# design.net
KiCad netlist of a schematic drawn in EasyEDA Pro
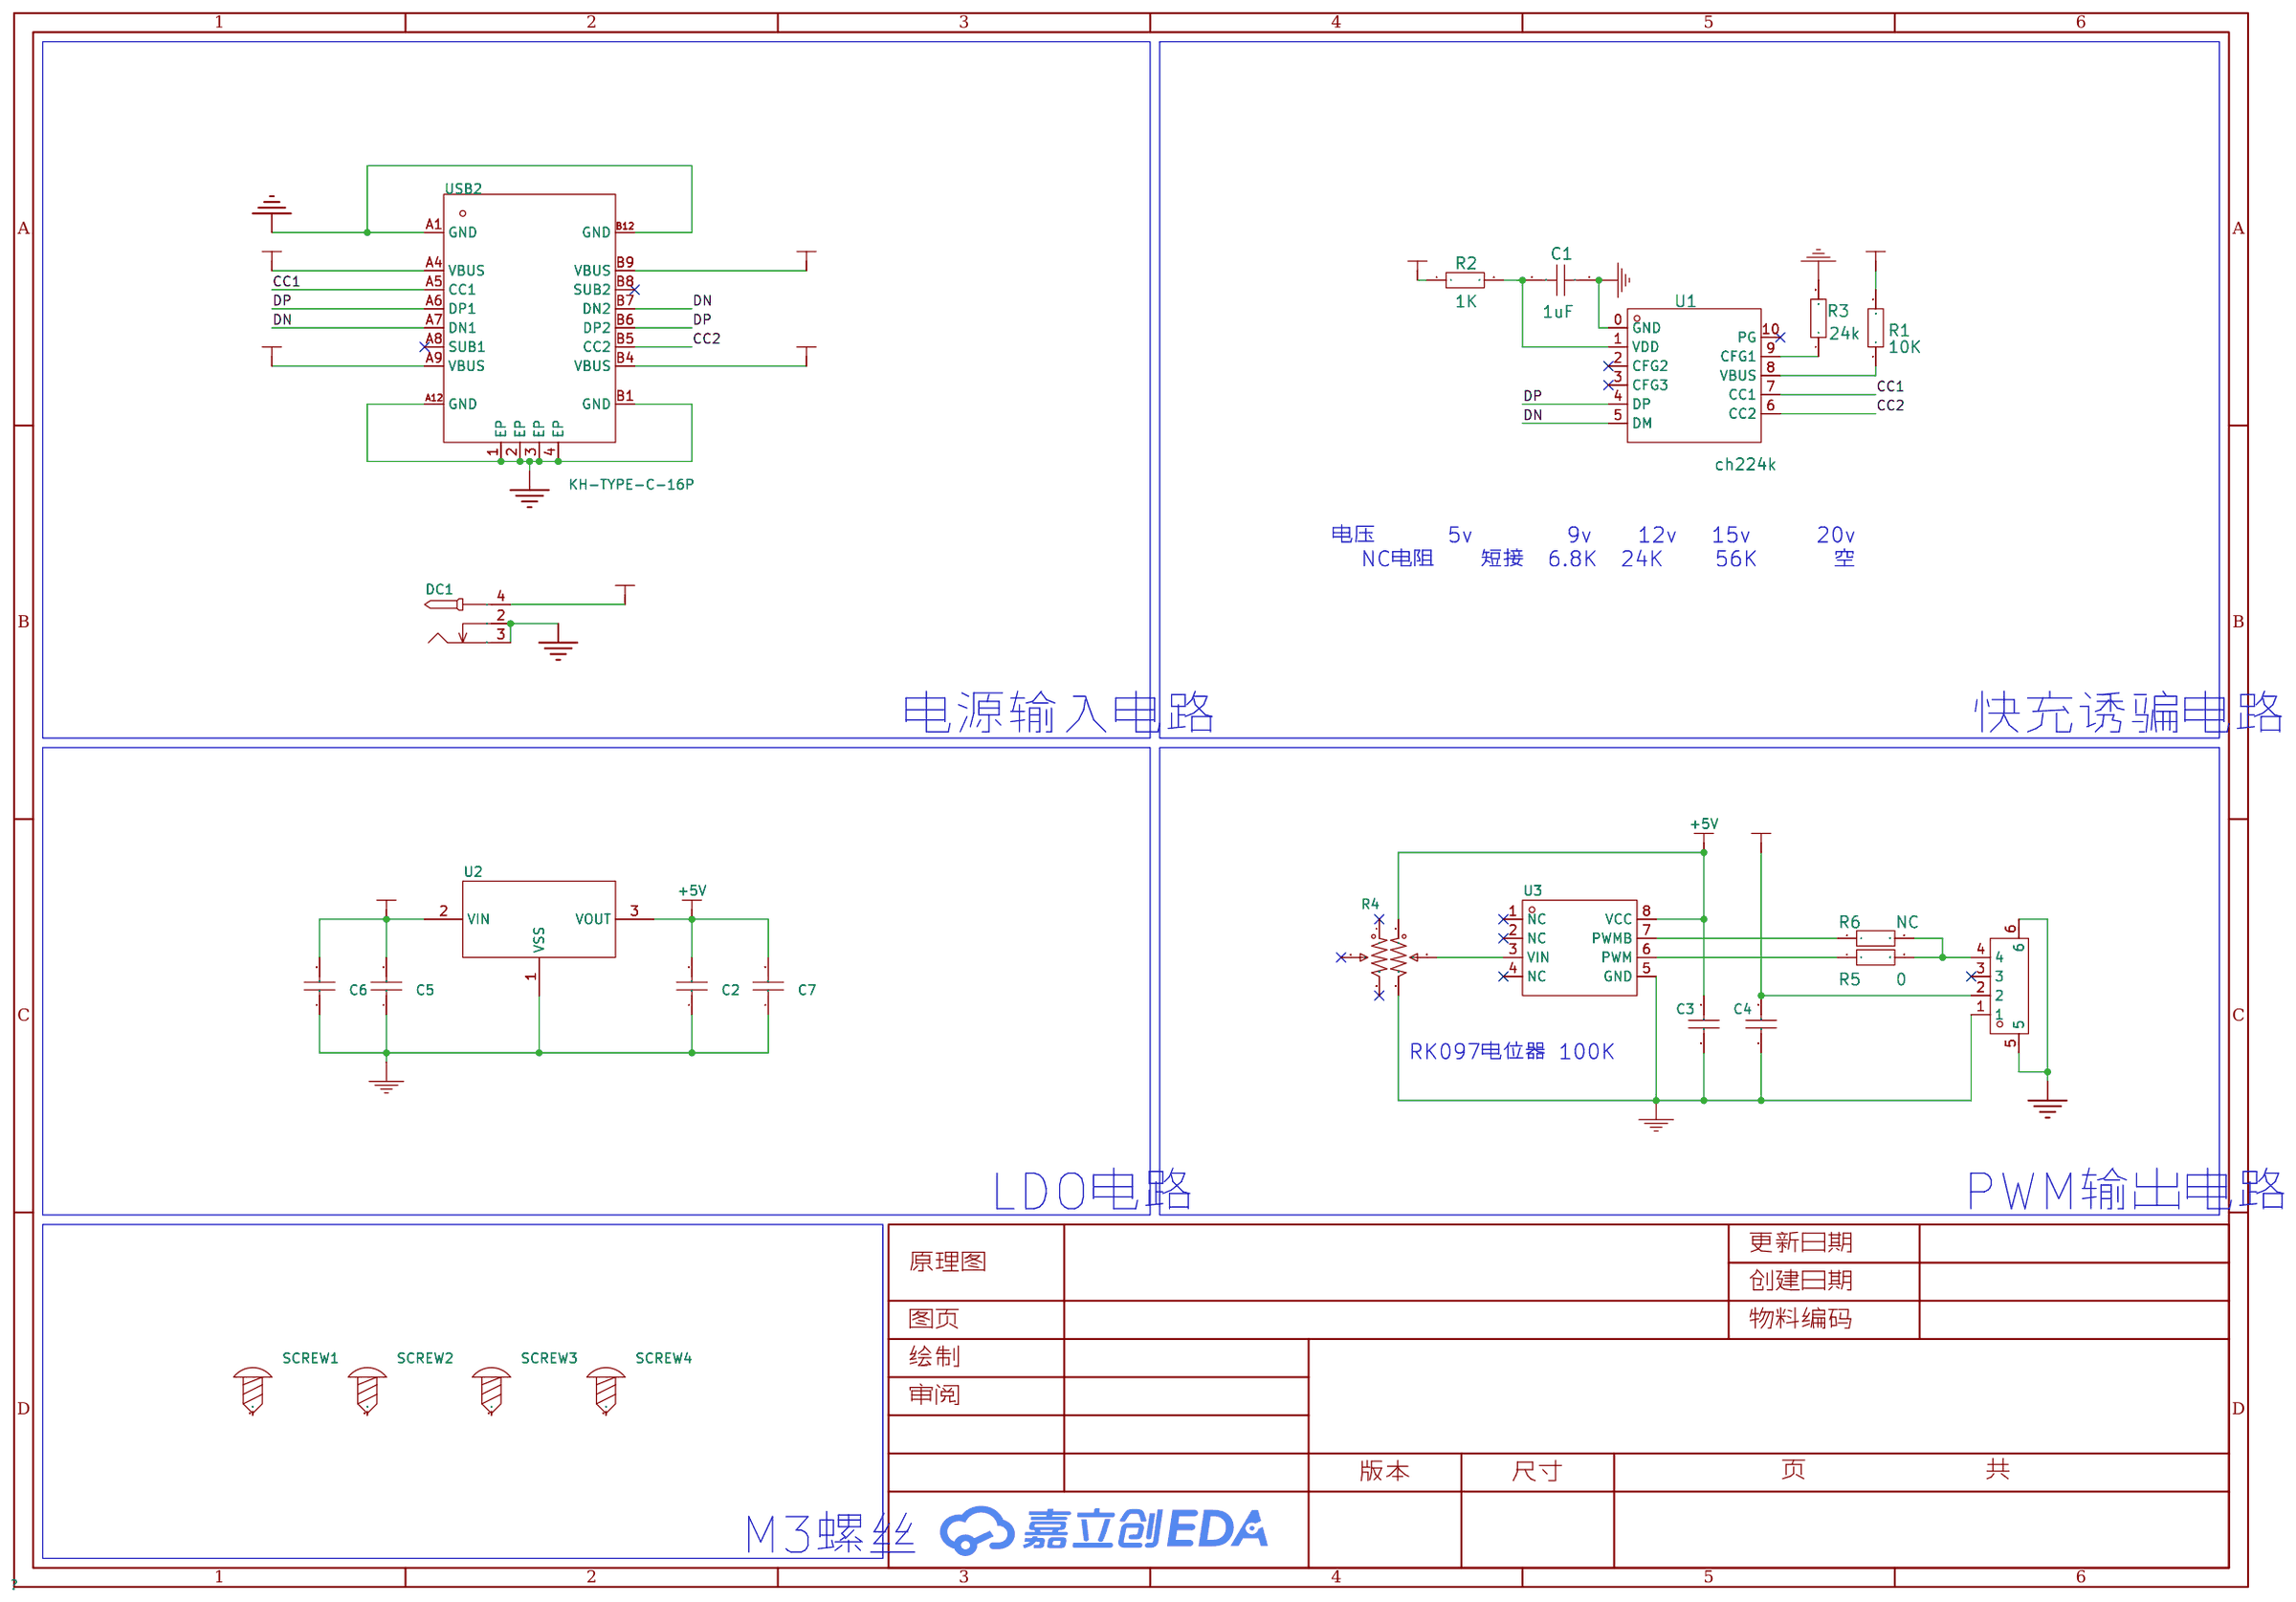
[diagram p0: schematic sheet]

(export (version "E")
  (design (tool "Eeschema 10.0.6"))
  (components
    (comp (ref "C1")
      (value "1uF")
      (footprint "easyedapro:C0805")
      (fields (field (name "Manufacturer Part") "CL10B104KC8NNNC") (field (name "Manufacturer") "SAMSUNG"))
      (libsource (lib "easyedapro") (part "1uF-10uF"))
    )
    (comp (ref "C2")
      (value "10uF")
      (fields
        (field (name "Manufacturer Part") "GRM188R6YA106MA73D")
        (field (name "Manufacturer") "muRata(村田)")
      )
      (libsource (lib "easyedapro") (part "CL10A106MO8NQNC"))
    )
    (comp (ref "C3")
      (value "10uF")
      (fields
        (field (name "Manufacturer Part") "GRM188R6YA106MA73D")
        (field (name "Manufacturer") "muRata(村田)")
      )
      (libsource (lib "easyedapro") (part "CL10A106MO8NQNC"))
    )
    (comp (ref "C4")
      (value "10uF")
      (fields
        (field (name "Manufacturer Part") "GRM188R6YA106MA73D")
        (field (name "Manufacturer") "muRata(村田)")
      )
      (libsource (lib "easyedapro") (part "CL10A106MO8NQNC"))
    )
    (comp (ref "C5")
      (value "10uF")
      (fields
        (field (name "Manufacturer Part") "GRM188R6YA106MA73D")
        (field (name "Manufacturer") "muRata(村田)")
      )
      (libsource (lib "easyedapro") (part "CL10A106MO8NQNC"))
    )
    (comp (ref "C6")
      (value "10uF")
      (fields
        (field (name "Manufacturer Part") "GRM188R6YA106MA73D")
        (field (name "Manufacturer") "muRata(村田)")
      )
      (libsource (lib "easyedapro") (part "CL10A106MO8NQNC"))
    )
    (comp (ref "C7")
      (value "10uF")
      (fields
        (field (name "Manufacturer Part") "GRM188R6YA106MA73D")
        (field (name "Manufacturer") "muRata(村田)")
      )
      (libsource (lib "easyedapro") (part "CL10A106MO8NQNC"))
    )
    (comp (ref "DC1")
      (value "~")
      (footprint "easyedapro:DC-2.0")
      (libsource (lib "easyedapro") (part "DC电源接口"))
    )
    (comp (ref "P2")
      (value "CONN-SMD_XH2.54-4PSMD")
      (footprint "easyedapro:CONN-SMD_XH2.54-4PSMD")
      (libsource (lib "easyedapro") (part "CONN-SMD_XH2.54-4PSMD"))
    )
    (comp (ref "R1")
      (value "10K")
      (footprint "easyedapro:R0805")
      (fields (field (name "Manufacturer Part") "0603WAJ0000T5E") (field (name "Manufacturer") "UniOhm"))
      (libsource (lib "easyedapro") (part "NC"))
    )
    (comp (ref "R2")
      (value "1K")
      (footprint "easyedapro:R0805")
      (fields (field (name "Manufacturer Part") "0603WAJ0000T5E") (field (name "Manufacturer") "UniOhm"))
      (libsource (lib "easyedapro") (part "NC"))
    )
    (comp (ref "R3")
      (value "24k")
      (footprint "easyedapro:R0805")
      (fields (field (name "Manufacturer Part") "0603WAJ0000T5E") (field (name "Manufacturer") "UniOhm"))
      (libsource (lib "easyedapro") (part "NC"))
    )
    (comp (ref "R4")
      (value "100kΩ")
      (footprint "easyedapro:RES-ADJ-TH_RK09712200MY")
      (description "阻值:10kΩ;精度:±20%;")
      (fields
        (field (name "Manufacturer Part") "RK09712200MY")
        (field (name "Manufacturer") "ALPSALPINE(阿尔卑斯阿尔派)")
      )
      (libsource (lib "easyedapro") (part "RK09712200MY"))
    )
    (comp (ref "R5")
      (value "0")
      (footprint "easyedapro:R0805")
      (fields (field (name "Manufacturer Part") "0603WAJ0000T5E") (field (name "Manufacturer") "UniOhm"))
      (libsource (lib "easyedapro") (part "NC"))
    )
    (comp (ref "R6")
      (value "NC")
      (footprint "easyedapro:R0805")
      (fields (field (name "Manufacturer Part") "0603WAJ0000T5E") (field (name "Manufacturer") "UniOhm"))
      (libsource (lib "easyedapro") (part "NC"))
    )
    (comp (ref "SCREW1")
      (value "~")
      (footprint "easyedapro:M3螺丝")
      (libsource (lib "easyedapro") (part "螺丝孔"))
    )
    (comp (ref "SCREW2")
      (value "~")
      (footprint "easyedapro:M3螺丝")
      (libsource (lib "easyedapro") (part "螺丝孔"))
    )
    (comp (ref "SCREW3")
      (value "~")
      (footprint "easyedapro:M3螺丝")
      (libsource (lib "easyedapro") (part "螺丝孔"))
    )
    (comp (ref "SCREW4")
      (value "~")
      (footprint "easyedapro:M3螺丝")
      (libsource (lib "easyedapro") (part "螺丝孔"))
    )
    (comp (ref "U1")
      (value "ch224k")
      (footprint "easyedapro:CH224K")
      (fields (field (name "Manufacturer Part") "CH224DS1") (field (name "Manufacturer") "WCH"))
      (libsource (lib "easyedapro") (part "ch224k"))
    )
    (comp (ref "U2")
      (value "ME6203A50PG")
      (footprint "easyedapro:SOT-89_L4.5-W2.5-P1.50-LS4.2-BR")
      (description "输出类型:固定;输出极性:正;输出通道数:1;最大输入电压:30V;输出电压:5V;压差:-;输出电流:100mA;电源纹波抑制比(PSRR):40dB@(1kHz);")
      (fields (field (name "Manufacturer") "MICRONE(南京微盟)"))
      (libsource (lib "easyedapro") (part "ME6203A50PG"))
    )
    (comp (ref "U3")
      (value "GP9101-F20K-L2H1-SW")
      (footprint "easyedapro:SOP-8_L5.0-W3.9-P1.27-LS6.0-BL")
      (description "GP9101 0-VCC转PWM 20KHz L2H1")
      (fields (field (name "Manufacturer") "Guestgood(客益)"))
      (libsource (lib "easyedapro") (part "GP9101-F20K-L2H1-SW"))
    )
    (comp (ref "USB2")
      (value "KH-TYPE-C-16P")
      (footprint "easyedapro:USB-C-SMD_KH-TYPE-C-16P")
      (description "连接器类型:Type-C;标准:-;公母:母;端口数量:1;触点数量:16P;安装方式:卧贴;额定电流 - 电源:3A;工作温度范围:-40°C~+85°C;")
      (fields (field (name "Manufacturer") "kinghelm(金航标)"))
      (libsource (lib "easyedapro") (part "KH-TYPE-C-16P"))
    )
  )
  (nets
    (net (code "1") (name "+5V") (class "Default")
      (node (ref "C2") (pin "2") (pinfunction "2_2") (pintype "input"))
      (node (ref "C3") (pin "2") (pinfunction "2_2") (pintype "input"))
      (node (ref "C7") (pin "2") (pinfunction "2_2") (pintype "input"))
      (node (ref "R4") (pin "1") (pinfunction "1_1") (pintype "input"))
      (node (ref "U2") (pin "3") (pinfunction "VOUT_3") (pintype "input"))
      (node (ref "U3") (pin "8") (pinfunction "VCC_8") (pintype "input"))
    )
    (net (code "2") (name "+12V") (class "Default")
      (node (ref "C4") (pin "2") (pinfunction "2_2") (pintype "input"))
      (node (ref "C5") (pin "2") (pinfunction "2_2") (pintype "input"))
      (node (ref "C6") (pin "2") (pinfunction "2_2") (pintype "input"))
      (node (ref "P2") (pin "2") (pinfunction "2_2") (pintype "input"))
      (node (ref "U2") (pin "2") (pinfunction "VIN_2") (pintype "input"))
    )
    (net (code "3") (name "/CC1") (class "Default")
      (node (ref "U1") (pin "7") (pinfunction "CC1_7") (pintype "input"))
      (node (ref "USB2") (pin "A5") (pinfunction "CC1_A5") (pintype "unspecified"))
    )
    (net (code "4") (name "/CC2") (class "Default")
      (node (ref "U1") (pin "6") (pinfunction "CC2_6") (pintype "input"))
      (node (ref "USB2") (pin "B5") (pinfunction "CC2_B5") (pintype "unspecified"))
    )
    (net (code "5") (name "/DN") (class "Default")
      (node (ref "U1") (pin "5") (pinfunction "DM_5") (pintype "input"))
      (node (ref "USB2") (pin "A7") (pinfunction "DN1_A7") (pintype "unspecified"))
      (node (ref "USB2") (pin "B7") (pinfunction "DN2_B7") (pintype "unspecified"))
    )
    (net (code "6") (name "/DP") (class "Default")
      (node (ref "U1") (pin "4") (pinfunction "DP_4") (pintype "input"))
      (node (ref "USB2") (pin "A6") (pinfunction "DP1_A6") (pintype "unspecified"))
      (node (ref "USB2") (pin "B6") (pinfunction "DP2_B6") (pintype "unspecified"))
    )
    (net (code "7") (name "GND") (class "Default")
      (node (ref "C1") (pin "1") (pinfunction "1_1") (pintype "input"))
      (node (ref "C2") (pin "1") (pinfunction "1_1") (pintype "input"))
      (node (ref "C3") (pin "1") (pinfunction "1_1") (pintype "input"))
      (node (ref "C4") (pin "1") (pinfunction "1_1") (pintype "input"))
      (node (ref "C5") (pin "1") (pinfunction "1_1") (pintype "input"))
      (node (ref "C6") (pin "1") (pinfunction "1_1") (pintype "input"))
      (node (ref "C7") (pin "1") (pinfunction "1_1") (pintype "input"))
      (node (ref "DC1") (pin "2") (pinfunction "2_2") (pintype "input"))
      (node (ref "DC1") (pin "3") (pinfunction "3_3") (pintype "input"))
      (node (ref "P2") (pin "1") (pinfunction "1_1") (pintype "input"))
      (node (ref "P2") (pin "5") (pinfunction "5_5") (pintype "input"))
      (node (ref "P2") (pin "6") (pinfunction "6_6") (pintype "input"))
      (node (ref "R3") (pin "2") (pinfunction "2_2") (pintype "input"))
      (node (ref "R4") (pin "3") (pinfunction "3_3") (pintype "input"))
      (node (ref "U1") (pin "0") (pinfunction "GND_0") (pintype "input"))
      (node (ref "U2") (pin "1") (pinfunction "VSS_1") (pintype "input"))
      (node (ref "U3") (pin "5") (pinfunction "GND_5") (pintype "input"))
      (node (ref "USB2") (pin "1") (pinfunction "EP_1") (pintype "unspecified"))
      (node (ref "USB2") (pin "2") (pinfunction "EP_2") (pintype "unspecified"))
      (node (ref "USB2") (pin "3") (pinfunction "EP_3") (pintype "unspecified"))
      (node (ref "USB2") (pin "4") (pinfunction "EP_4") (pintype "unspecified"))
      (node (ref "USB2") (pin "A1") (pinfunction "GND_A1") (pintype "unspecified"))
      (node (ref "USB2") (pin "A12") (pinfunction "GND_A12") (pintype "unspecified"))
      (node (ref "USB2") (pin "B1") (pinfunction "GND_B1") (pintype "unspecified"))
      (node (ref "USB2") (pin "B12") (pinfunction "GND_B12") (pintype "unspecified"))
    )
    (net (code "8") (name "Net-(P2-Pad4)") (class "Default")
      (node (ref "P2") (pin "4") (pinfunction "4_4") (pintype "input"))
      (node (ref "R5") (pin "2") (pinfunction "2_2") (pintype "input"))
      (node (ref "R6") (pin "2") (pinfunction "2_2") (pintype "input"))
    )
    (net (code "9") (name "Net-(U1-CFG1)") (class "Default")
      (node (ref "R3") (pin "1") (pinfunction "1_1") (pintype "input"))
      (node (ref "U1") (pin "9") (pinfunction "CFG1_9") (pintype "input"))
    )
    (net (code "10") (name "Net-(U1-VBUS)") (class "Default")
      (node (ref "R1") (pin "1") (pinfunction "1_1") (pintype "input"))
      (node (ref "U1") (pin "8") (pinfunction "VBUS_8") (pintype "input"))
    )
    (net (code "11") (name "Net-(U1-VDD)") (class "Default")
      (node (ref "C1") (pin "2") (pinfunction "2_2") (pintype "input"))
      (node (ref "R2") (pin "2") (pinfunction "2_2") (pintype "input"))
      (node (ref "U1") (pin "1") (pinfunction "VDD_1") (pintype "input"))
    )
    (net (code "12") (name "Net-(U3-PWM)") (class "Default")
      (node (ref "R5") (pin "1") (pinfunction "1_1") (pintype "input"))
      (node (ref "U3") (pin "6") (pinfunction "PWM_6") (pintype "input"))
    )
    (net (code "13") (name "Net-(U3-PWMB)") (class "Default")
      (node (ref "R6") (pin "1") (pinfunction "1_1") (pintype "input"))
      (node (ref "U3") (pin "7") (pinfunction "PWMB_7") (pintype "input"))
    )
    (net (code "14") (name "Net-(U3-VIN)") (class "Default")
      (node (ref "R4") (pin "2") (pinfunction "2_2") (pintype "input"))
      (node (ref "U3") (pin "3") (pinfunction "VIN_3") (pintype "input"))
    )
    (net (code "15") (name "VBUS") (class "Default")
      (node (ref "DC1") (pin "4") (pinfunction "4_4") (pintype "input"))
      (node (ref "R1") (pin "2") (pinfunction "2_2") (pintype "input"))
      (node (ref "R2") (pin "1") (pinfunction "1_1") (pintype "input"))
      (node (ref "USB2") (pin "A4") (pinfunction "VBUS_A4") (pintype "unspecified"))
      (node (ref "USB2") (pin "A9") (pinfunction "VBUS_A9") (pintype "unspecified"))
      (node (ref "USB2") (pin "B4") (pinfunction "VBUS_B4") (pintype "unspecified"))
      (node (ref "USB2") (pin "B9") (pinfunction "VBUS_B9") (pintype "unspecified"))
    )
    (net (code "16") (name "unconnected-(P2-Pad3)") (class "Default")
      (node (ref "P2") (pin "3") (pinfunction "3_3") (pintype "input+no_connect"))
    )
    (net (code "17") (name "unconnected-(R4-Pad4)") (class "Default")
      (node (ref "R4") (pin "4") (pinfunction "4_4") (pintype "input+no_connect"))
    )
    (net (code "18") (name "unconnected-(R4-Pad5)") (class "Default")
      (node (ref "R4") (pin "5") (pinfunction "5_5") (pintype "input+no_connect"))
    )
    (net (code "19") (name "unconnected-(R4-Pad6)") (class "Default")
      (node (ref "R4") (pin "6") (pinfunction "6_6") (pintype "input+no_connect"))
    )
    (net (code "20") (name "unconnected-(SCREW1-Pad1)") (class "Default")
      (node (ref "SCREW1") (pin "1") (pinfunction "1_1") (pintype "input"))
    )
    (net (code "21") (name "unconnected-(SCREW2-Pad1)") (class "Default")
      (node (ref "SCREW2") (pin "1") (pinfunction "1_1") (pintype "input"))
    )
    (net (code "22") (name "unconnected-(SCREW3-Pad1)") (class "Default")
      (node (ref "SCREW3") (pin "1") (pinfunction "1_1") (pintype "input"))
    )
    (net (code "23") (name "unconnected-(SCREW4-Pad1)") (class "Default")
      (node (ref "SCREW4") (pin "1") (pinfunction "1_1") (pintype "input"))
    )
    (net (code "24") (name "unconnected-(U1-CFG2-Pad2)") (class "Default")
      (node (ref "U1") (pin "2") (pinfunction "CFG2_2") (pintype "input+no_connect"))
    )
    (net (code "25") (name "unconnected-(U1-CFG3-Pad3)") (class "Default")
      (node (ref "U1") (pin "3") (pinfunction "CFG3_3") (pintype "input+no_connect"))
    )
    (net (code "26") (name "unconnected-(U1-PG-Pad10)") (class "Default")
      (node (ref "U1") (pin "10") (pinfunction "PG_10") (pintype "input+no_connect"))
    )
    (net (code "27") (name "unconnected-(U3-NC-Pad1)") (class "Default")
      (node (ref "U3") (pin "1") (pinfunction "NC_1") (pintype "input+no_connect"))
    )
    (net (code "28") (name "unconnected-(U3-NC-Pad2)") (class "Default")
      (node (ref "U3") (pin "2") (pinfunction "NC_2") (pintype "input+no_connect"))
    )
    (net (code "29") (name "unconnected-(U3-NC-Pad4)") (class "Default")
      (node (ref "U3") (pin "4") (pinfunction "NC_4") (pintype "input+no_connect"))
    )
    (net (code "30") (name "unconnected-(USB2-SUB1-PadA8)") (class "Default")
      (node (ref "USB2") (pin "A8") (pinfunction "SUB1_A8") (pintype "unspecified+no_connect"))
    )
    (net (code "31") (name "unconnected-(USB2-SUB2-PadB8)") (class "Default")
      (node (ref "USB2") (pin "B8") (pinfunction "SUB2_B8") (pintype "unspecified+no_connect"))
    )
  )
)
